# 3x3_LED.net
KiCad netlist of a schematic drawn in EAGLE
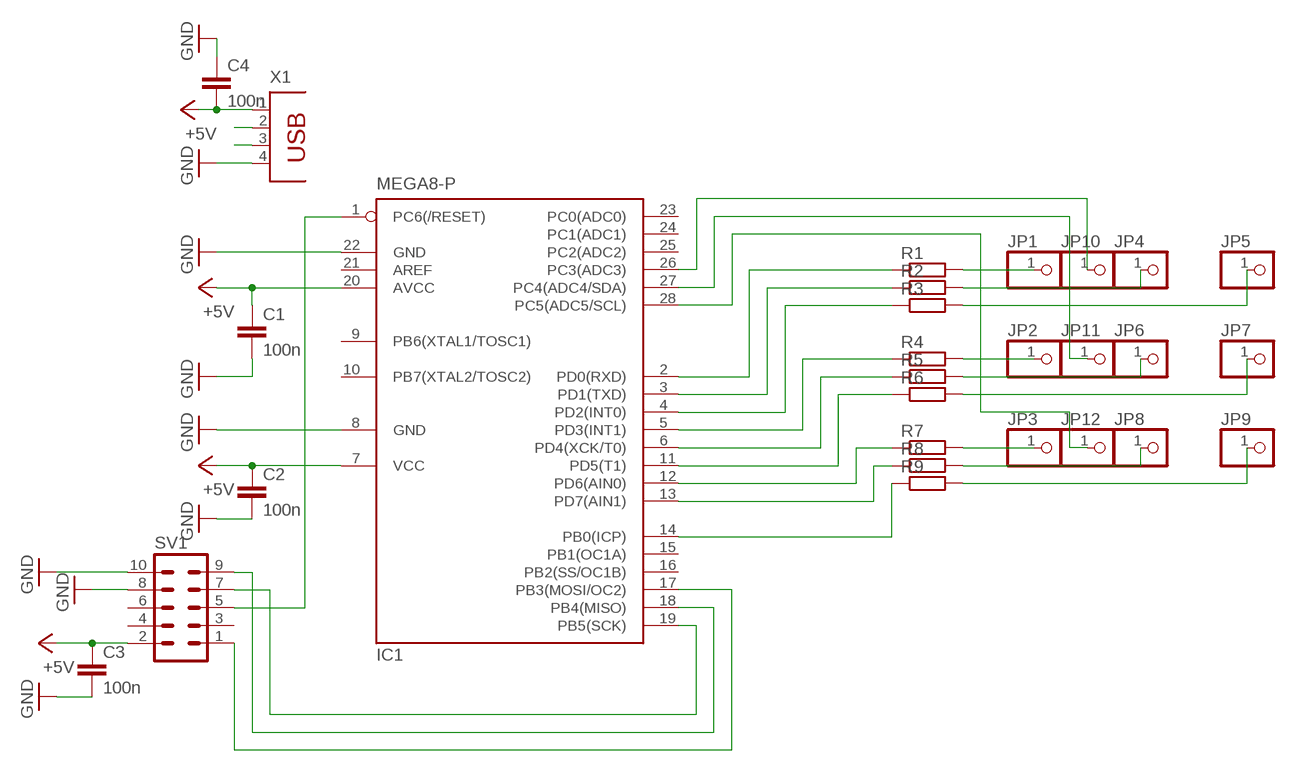
[diagram p0: schematic, sheet 1]

(export (version "E")
  (design (tool "Eeschema 10.0.6"))
  (components
    (comp (ref "C1")
      (value "100n")
      (footprint "eagle-import:C025-024X044")
      (libsource (lib "eagle-import") (part "C-EU025-024X044"))
    )
    (comp (ref "C2")
      (value "100n")
      (footprint "eagle-import:C025-024X044")
      (libsource (lib "eagle-import") (part "C-EU025-024X044"))
    )
    (comp (ref "C3")
      (value "100n")
      (footprint "eagle-import:C025-024X044")
      (libsource (lib "eagle-import") (part "C-EU025-024X044"))
    )
    (comp (ref "C4")
      (value "100n")
      (footprint "eagle-import:C025-024X044")
      (libsource (lib "eagle-import") (part "C-EU025-024X044"))
    )
    (comp (ref "IC1")
      (value "MEGA8-P")
      (footprint "eagle-import:DIL28-3")
      (libsource (lib "eagle-import") (part "MEGA8-P"))
    )
    (comp (ref "JP1")
      (value "PINHD-1X1")
      (footprint "eagle-import:1X01")
      (libsource (lib "eagle-import") (part "PINHD-1X1"))
    )
    (comp (ref "JP2")
      (value "PINHD-1X1")
      (footprint "eagle-import:1X01")
      (libsource (lib "eagle-import") (part "PINHD-1X1"))
    )
    (comp (ref "JP3")
      (value "PINHD-1X1")
      (footprint "eagle-import:1X01")
      (libsource (lib "eagle-import") (part "PINHD-1X1"))
    )
    (comp (ref "JP4")
      (value "PINHD-1X1")
      (footprint "eagle-import:1X01")
      (libsource (lib "eagle-import") (part "PINHD-1X1"))
    )
    (comp (ref "JP5")
      (value "PINHD-1X1")
      (footprint "eagle-import:1X01")
      (libsource (lib "eagle-import") (part "PINHD-1X1"))
    )
    (comp (ref "JP6")
      (value "PINHD-1X1")
      (footprint "eagle-import:1X01")
      (libsource (lib "eagle-import") (part "PINHD-1X1"))
    )
    (comp (ref "JP7")
      (value "PINHD-1X1")
      (footprint "eagle-import:1X01")
      (libsource (lib "eagle-import") (part "PINHD-1X1"))
    )
    (comp (ref "JP8")
      (value "PINHD-1X1")
      (footprint "eagle-import:1X01")
      (libsource (lib "eagle-import") (part "PINHD-1X1"))
    )
    (comp (ref "JP9")
      (value "PINHD-1X1")
      (footprint "eagle-import:1X01")
      (libsource (lib "eagle-import") (part "PINHD-1X1"))
    )
    (comp (ref "JP10")
      (value "PINHD-1X1")
      (footprint "eagle-import:1X01")
      (libsource (lib "eagle-import") (part "PINHD-1X1"))
    )
    (comp (ref "JP11")
      (value "PINHD-1X1")
      (footprint "eagle-import:1X01")
      (libsource (lib "eagle-import") (part "PINHD-1X1"))
    )
    (comp (ref "JP12")
      (value "PINHD-1X1")
      (footprint "eagle-import:1X01")
      (libsource (lib "eagle-import") (part "PINHD-1X1"))
    )
    (comp (ref "R1")
      (value "R-EU_0207/12")
      (footprint "eagle-import:0207_12")
      (libsource (lib "eagle-import") (part "R-EU_0207/12"))
    )
    (comp (ref "R2")
      (value "R-EU_0207/12")
      (footprint "eagle-import:0207_12")
      (libsource (lib "eagle-import") (part "R-EU_0207/12"))
    )
    (comp (ref "R3")
      (value "R-EU_0207/12")
      (footprint "eagle-import:0207_12")
      (libsource (lib "eagle-import") (part "R-EU_0207/12"))
    )
    (comp (ref "R4")
      (value "R-EU_0207/12")
      (footprint "eagle-import:0207_12")
      (libsource (lib "eagle-import") (part "R-EU_0207/12"))
    )
    (comp (ref "R5")
      (value "R-EU_0207/12")
      (footprint "eagle-import:0207_12")
      (libsource (lib "eagle-import") (part "R-EU_0207/12"))
    )
    (comp (ref "R6")
      (value "R-EU_0207/12")
      (footprint "eagle-import:0207_12")
      (libsource (lib "eagle-import") (part "R-EU_0207/12"))
    )
    (comp (ref "R7")
      (value "R-EU_0207/12")
      (footprint "eagle-import:0207_12")
      (libsource (lib "eagle-import") (part "R-EU_0207/12"))
    )
    (comp (ref "R8")
      (value "R-EU_0207/12")
      (footprint "eagle-import:0207_12")
      (libsource (lib "eagle-import") (part "R-EU_0207/12"))
    )
    (comp (ref "R9")
      (value "R-EU_0207/12")
      (footprint "eagle-import:0207_12")
      (libsource (lib "eagle-import") (part "R-EU_0207/12"))
    )
    (comp (ref "SV1")
      (value "ML10")
      (footprint "eagle-import:ML10")
      (libsource (lib "eagle-import") (part "ML10"))
    )
    (comp (ref "X1")
      (value "PN61729")
      (footprint "eagle-import:PN61729")
      (libsource (lib "eagle-import") (part "PN61729"))
    )
  )
  (nets
    (net (code "1") (name "+5V") (class "Default")
      (node (ref "C1") (pin "1") (pinfunction "1_1") (pintype "passive"))
      (node (ref "C2") (pin "1") (pinfunction "1_1") (pintype "passive"))
      (node (ref "C3") (pin "1") (pinfunction "1_1") (pintype "passive"))
      (node (ref "C4") (pin "2") (pinfunction "2_2") (pintype "passive"))
      (node (ref "IC1") (pin "20") (pinfunction "AVCC_20") (pintype "power_in"))
      (node (ref "IC1") (pin "7") (pinfunction "VCC_7") (pintype "power_in"))
      (node (ref "SV1") (pin "2") (pinfunction "2_2") (pintype "passive"))
      (node (ref "X1") (pin "1") (pinfunction "1_1") (pintype "passive"))
    )
    (net (code "2") (name "GND") (class "Default")
      (node (ref "C1") (pin "2") (pinfunction "2_2") (pintype "passive"))
      (node (ref "C2") (pin "2") (pinfunction "2_2") (pintype "passive"))
      (node (ref "C3") (pin "2") (pinfunction "2_2") (pintype "passive"))
      (node (ref "C4") (pin "1") (pinfunction "1_1") (pintype "passive"))
      (node (ref "IC1") (pin "22") (pinfunction "GND_22") (pintype "power_in"))
      (node (ref "IC1") (pin "8") (pinfunction "GND_8") (pintype "power_in"))
      (node (ref "SV1") (pin "10") (pinfunction "10_10") (pintype "passive"))
      (node (ref "SV1") (pin "8") (pinfunction "8_8") (pintype "passive"))
      (node (ref "X1") (pin "4") (pinfunction "4_4") (pintype "passive"))
    )
    (net (code "3") (name "Net-(IC1-PB0(ICP))") (class "Default")
      (node (ref "IC1") (pin "14") (pinfunction "PB0(ICP)_14") (pintype "bidirectional"))
      (node (ref "R9") (pin "1") (pinfunction "1_1") (pintype "passive"))
    )
    (net (code "4") (name "Net-(IC1-PB3(MOSI{slash}OC2))") (class "Default")
      (node (ref "IC1") (pin "17") (pinfunction "PB3(MOSI/OC2)_17") (pintype "bidirectional"))
      (node (ref "SV1") (pin "1") (pinfunction "1_1") (pintype "passive"))
    )
    (net (code "5") (name "Net-(IC1-PB4(MISO))") (class "Default")
      (node (ref "IC1") (pin "18") (pinfunction "PB4(MISO)_18") (pintype "bidirectional"))
      (node (ref "SV1") (pin "9") (pinfunction "9_9") (pintype "passive"))
    )
    (net (code "6") (name "Net-(IC1-PB5(SCK))") (class "Default")
      (node (ref "IC1") (pin "19") (pinfunction "PB5(SCK)_19") (pintype "bidirectional"))
      (node (ref "SV1") (pin "7") (pinfunction "7_7") (pintype "passive"))
    )
    (net (code "7") (name "Net-(IC1-PC3(ADC3))") (class "Default")
      (node (ref "IC1") (pin "26") (pinfunction "PC3(ADC3)_26") (pintype "bidirectional"))
      (node (ref "JP10") (pin "1") (pinfunction "1_1") (pintype "passive"))
    )
    (net (code "8") (name "Net-(IC1-PC4(ADC4{slash}SDA))") (class "Default")
      (node (ref "IC1") (pin "27") (pinfunction "PC4(ADC4/SDA)_27") (pintype "bidirectional"))
      (node (ref "JP11") (pin "1") (pinfunction "1_1") (pintype "passive"))
    )
    (net (code "9") (name "Net-(IC1-PC5(ADC5{slash}SCL))") (class "Default")
      (node (ref "IC1") (pin "28") (pinfunction "PC5(ADC5/SCL)_28") (pintype "bidirectional"))
      (node (ref "JP12") (pin "1") (pinfunction "1_1") (pintype "passive"))
    )
    (net (code "10") (name "Net-(IC1-PC6({slash}RESET))") (class "Default")
      (node (ref "IC1") (pin "1") (pinfunction "PC6(/RESET)_1") (pintype "bidirectional"))
      (node (ref "SV1") (pin "5") (pinfunction "5_5") (pintype "passive"))
    )
    (net (code "11") (name "Net-(IC1-PD0(RXD))") (class "Default")
      (node (ref "IC1") (pin "2") (pinfunction "PD0(RXD)_2") (pintype "bidirectional"))
      (node (ref "R1") (pin "1") (pinfunction "1_1") (pintype "passive"))
    )
    (net (code "12") (name "Net-(IC1-PD1(TXD))") (class "Default")
      (node (ref "IC1") (pin "3") (pinfunction "PD1(TXD)_3") (pintype "bidirectional"))
      (node (ref "R2") (pin "1") (pinfunction "1_1") (pintype "passive"))
    )
    (net (code "13") (name "Net-(IC1-PD2(INT0))") (class "Default")
      (node (ref "IC1") (pin "4") (pinfunction "PD2(INT0)_4") (pintype "bidirectional"))
      (node (ref "R3") (pin "1") (pinfunction "1_1") (pintype "passive"))
    )
    (net (code "14") (name "Net-(IC1-PD3(INT1))") (class "Default")
      (node (ref "IC1") (pin "5") (pinfunction "PD3(INT1)_5") (pintype "bidirectional"))
      (node (ref "R4") (pin "1") (pinfunction "1_1") (pintype "passive"))
    )
    (net (code "15") (name "Net-(IC1-PD4(XCK{slash}T0))") (class "Default")
      (node (ref "IC1") (pin "6") (pinfunction "PD4(XCK/T0)_6") (pintype "bidirectional"))
      (node (ref "R5") (pin "1") (pinfunction "1_1") (pintype "passive"))
    )
    (net (code "16") (name "Net-(IC1-PD5(T1))") (class "Default")
      (node (ref "IC1") (pin "11") (pinfunction "PD5(T1)_11") (pintype "bidirectional"))
      (node (ref "R6") (pin "1") (pinfunction "1_1") (pintype "passive"))
    )
    (net (code "17") (name "Net-(IC1-PD6(AIN0))") (class "Default")
      (node (ref "IC1") (pin "12") (pinfunction "PD6(AIN0)_12") (pintype "bidirectional"))
      (node (ref "R7") (pin "1") (pinfunction "1_1") (pintype "passive"))
    )
    (net (code "18") (name "Net-(IC1-PD7(AIN1))") (class "Default")
      (node (ref "IC1") (pin "13") (pinfunction "PD7(AIN1)_13") (pintype "bidirectional"))
      (node (ref "R8") (pin "1") (pinfunction "1_1") (pintype "passive"))
    )
    (net (code "19") (name "Net-(JP1-Pad1)") (class "Default")
      (node (ref "JP1") (pin "1") (pinfunction "1_1") (pintype "passive"))
      (node (ref "R1") (pin "2") (pinfunction "2_2") (pintype "passive"))
    )
    (net (code "20") (name "Net-(JP2-Pad1)") (class "Default")
      (node (ref "JP2") (pin "1") (pinfunction "1_1") (pintype "passive"))
      (node (ref "R4") (pin "2") (pinfunction "2_2") (pintype "passive"))
    )
    (net (code "21") (name "Net-(JP3-Pad1)") (class "Default")
      (node (ref "JP3") (pin "1") (pinfunction "1_1") (pintype "passive"))
      (node (ref "R7") (pin "2") (pinfunction "2_2") (pintype "passive"))
    )
    (net (code "22") (name "Net-(JP4-Pad1)") (class "Default")
      (node (ref "JP4") (pin "1") (pinfunction "1_1") (pintype "passive"))
      (node (ref "R2") (pin "2") (pinfunction "2_2") (pintype "passive"))
    )
    (net (code "23") (name "Net-(JP5-Pad1)") (class "Default")
      (node (ref "JP5") (pin "1") (pinfunction "1_1") (pintype "passive"))
      (node (ref "R3") (pin "2") (pinfunction "2_2") (pintype "passive"))
    )
    (net (code "24") (name "Net-(JP6-Pad1)") (class "Default")
      (node (ref "JP6") (pin "1") (pinfunction "1_1") (pintype "passive"))
      (node (ref "R5") (pin "2") (pinfunction "2_2") (pintype "passive"))
    )
    (net (code "25") (name "Net-(JP7-Pad1)") (class "Default")
      (node (ref "JP7") (pin "1") (pinfunction "1_1") (pintype "passive"))
      (node (ref "R6") (pin "2") (pinfunction "2_2") (pintype "passive"))
    )
    (net (code "26") (name "Net-(JP8-Pad1)") (class "Default")
      (node (ref "JP8") (pin "1") (pinfunction "1_1") (pintype "passive"))
      (node (ref "R8") (pin "2") (pinfunction "2_2") (pintype "passive"))
    )
    (net (code "27") (name "Net-(JP9-Pad1)") (class "Default")
      (node (ref "JP9") (pin "1") (pinfunction "1_1") (pintype "passive"))
      (node (ref "R9") (pin "2") (pinfunction "2_2") (pintype "passive"))
    )
    (net (code "28") (name "unconnected-(IC1-AREF-Pad21)") (class "Default")
      (node (ref "IC1") (pin "21") (pinfunction "AREF_21") (pintype "passive"))
    )
    (net (code "29") (name "unconnected-(IC1-PB1(OC1A)-Pad15)") (class "Default")
      (node (ref "IC1") (pin "15") (pinfunction "PB1(OC1A)_15") (pintype "bidirectional"))
    )
    (net (code "30") (name "unconnected-(IC1-PB2(SS{slash}OC1B)-Pad16)") (class "Default")
      (node (ref "IC1") (pin "16") (pinfunction "PB2(SS/OC1B)_16") (pintype "bidirectional"))
    )
    (net (code "31") (name "unconnected-(IC1-PB6(XTAL1{slash}TOSC1)-Pad9)") (class "Default")
      (node (ref "IC1") (pin "9") (pinfunction "PB6(XTAL1/TOSC1)_9") (pintype "bidirectional"))
    )
    (net (code "32") (name "unconnected-(IC1-PB7(XTAL2{slash}TOSC2)-Pad10)") (class "Default")
      (node (ref "IC1") (pin "10") (pinfunction "PB7(XTAL2/TOSC2)_10") (pintype "bidirectional"))
    )
    (net (code "33") (name "unconnected-(IC1-PC0(ADC0)-Pad23)") (class "Default")
      (node (ref "IC1") (pin "23") (pinfunction "PC0(ADC0)_23") (pintype "bidirectional"))
    )
    (net (code "34") (name "unconnected-(IC1-PC1(ADC1)-Pad24)") (class "Default")
      (node (ref "IC1") (pin "24") (pinfunction "PC1(ADC1)_24") (pintype "bidirectional"))
    )
    (net (code "35") (name "unconnected-(IC1-PC2(ADC2)-Pad25)") (class "Default")
      (node (ref "IC1") (pin "25") (pinfunction "PC2(ADC2)_25") (pintype "bidirectional"))
    )
    (net (code "36") (name "unconnected-(SV1-Pad3)") (class "Default")
      (node (ref "SV1") (pin "3") (pinfunction "3_3") (pintype "passive"))
    )
    (net (code "37") (name "unconnected-(SV1-Pad4)") (class "Default")
      (node (ref "SV1") (pin "4") (pinfunction "4_4") (pintype "passive"))
    )
    (net (code "38") (name "unconnected-(SV1-Pad6)") (class "Default")
      (node (ref "SV1") (pin "6") (pinfunction "6_6") (pintype "passive"))
    )
    (net (code "39") (name "unconnected-(X1-Pad2)") (class "Default")
      (node (ref "X1") (pin "2") (pinfunction "2_2") (pintype "passive"))
    )
    (net (code "40") (name "unconnected-(X1-Pad3)") (class "Default")
      (node (ref "X1") (pin "3") (pinfunction "3_3") (pintype "passive"))
    )
  )
)
